# SCH_Inductor_board.net
KiCad netlist of a schematic drawn in Altium Designer
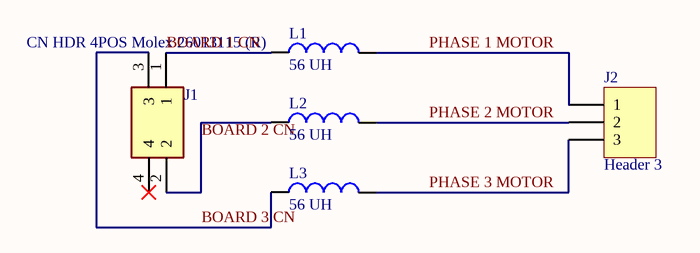
[diagram p0: SCH_Inductor_board.SchDoc]

(export (version "E")
  (design (tool "Eeschema 10.0.6"))
  (components
    (comp (ref "J1")
      (value "CN HDR 4POS Molex 26013115 (R)")
      (footprint "26013115")
      (description "Molex 26013115 4POS Minifit\r\ndual row, right angle")
      (libsource (lib "AltiumLibraries") (part "CN HDR 4POS Molex 26013115 (R)"))
    )
    (comp (ref "J2")
      (value "Header 3")
      (footprint "HDR1X3")
      (description "Header, 3-Pin")
      (fields (field (name "PUBLISHER") "Altium Limited"))
      (libsource (lib "Miscellaneous Connectors") (part "Header 3"))
    )
    (comp (ref "L1")
      (value "56 UH")
      (footprint "EATON _HCM1A1307V2-560-R")
      (description "FIXED!! IND 56UH 4A 65 MOHM SMD Shielded - Inductor 65mOhm Max Nonstandard -")
      (fields (field (name "DIGI-KEY PART NUMBER") "283-HCM1A1307V2-560-RTR-ND"))
      (libsource (lib "AltiumLibraries") (part "IND 56UH 4A 65 mOHM SMD"))
    )
    (comp (ref "L2")
      (value "56 UH")
      (footprint "EATON _HCM1A1307V2-560-R")
      (description "FIXED!! IND 56UH 4A 65 MOHM SMD Shielded - Inductor 65mOhm Max Nonstandard -")
      (fields (field (name "DIGI-KEY PART NUMBER") "283-HCM1A1307V2-560-RTR-ND"))
      (libsource (lib "AltiumLibraries") (part "IND 56UH 4A 65 mOHM SMD"))
    )
    (comp (ref "L3")
      (value "56 UH")
      (footprint "EATON _HCM1A1307V2-560-R")
      (description "FIXED!! IND 56UH 4A 65 MOHM SMD Shielded - Inductor 65mOhm Max Nonstandard -")
      (fields (field (name "DIGI-KEY PART NUMBER") "283-HCM1A1307V2-560-RTR-ND"))
      (libsource (lib "AltiumLibraries") (part "IND 56UH 4A 65 mOHM SMD"))
    )
  )
  (nets
    (net (code "1") (name "/BOARD 1 CN") (class "Default")
      (node (ref "J1") (pin "1") (pinfunction "1_1") (pintype "passive"))
      (node (ref "L1") (pin "1") (pinfunction "1_1") (pintype "passive"))
    )
    (net (code "2") (name "/BOARD 2 CN") (class "Default")
      (node (ref "J1") (pin "2") (pinfunction "2_2") (pintype "passive"))
      (node (ref "L2") (pin "1") (pinfunction "1_1") (pintype "passive"))
    )
    (net (code "3") (name "/BOARD 3 CN") (class "Default")
      (node (ref "J1") (pin "3") (pinfunction "3_3") (pintype "passive"))
      (node (ref "L3") (pin "1") (pinfunction "1_1") (pintype "passive"))
    )
    (net (code "4") (name "/PHASE 1 MOTOR") (class "Default")
      (node (ref "J2") (pin "1") (pinfunction "1_1") (pintype "passive"))
      (node (ref "L1") (pin "2") (pinfunction "2_2") (pintype "passive"))
    )
    (net (code "5") (name "/PHASE 2 MOTOR") (class "Default")
      (node (ref "J2") (pin "2") (pinfunction "2_2") (pintype "passive"))
      (node (ref "L2") (pin "2") (pinfunction "2_2") (pintype "passive"))
    )
    (net (code "6") (name "/PHASE 3 MOTOR") (class "Default")
      (node (ref "J2") (pin "3") (pinfunction "3_3") (pintype "passive"))
      (node (ref "L3") (pin "2") (pinfunction "2_2") (pintype "passive"))
    )
    (net (code "7") (name "unconnected-(J1-Pad4)") (class "Default")
      (node (ref "J1") (pin "4") (pinfunction "4_4") (pintype "passive+no_connect"))
    )
  )
)
